# FLYTE-v2_1.net
KiCad netlist of a schematic drawn in EAGLE
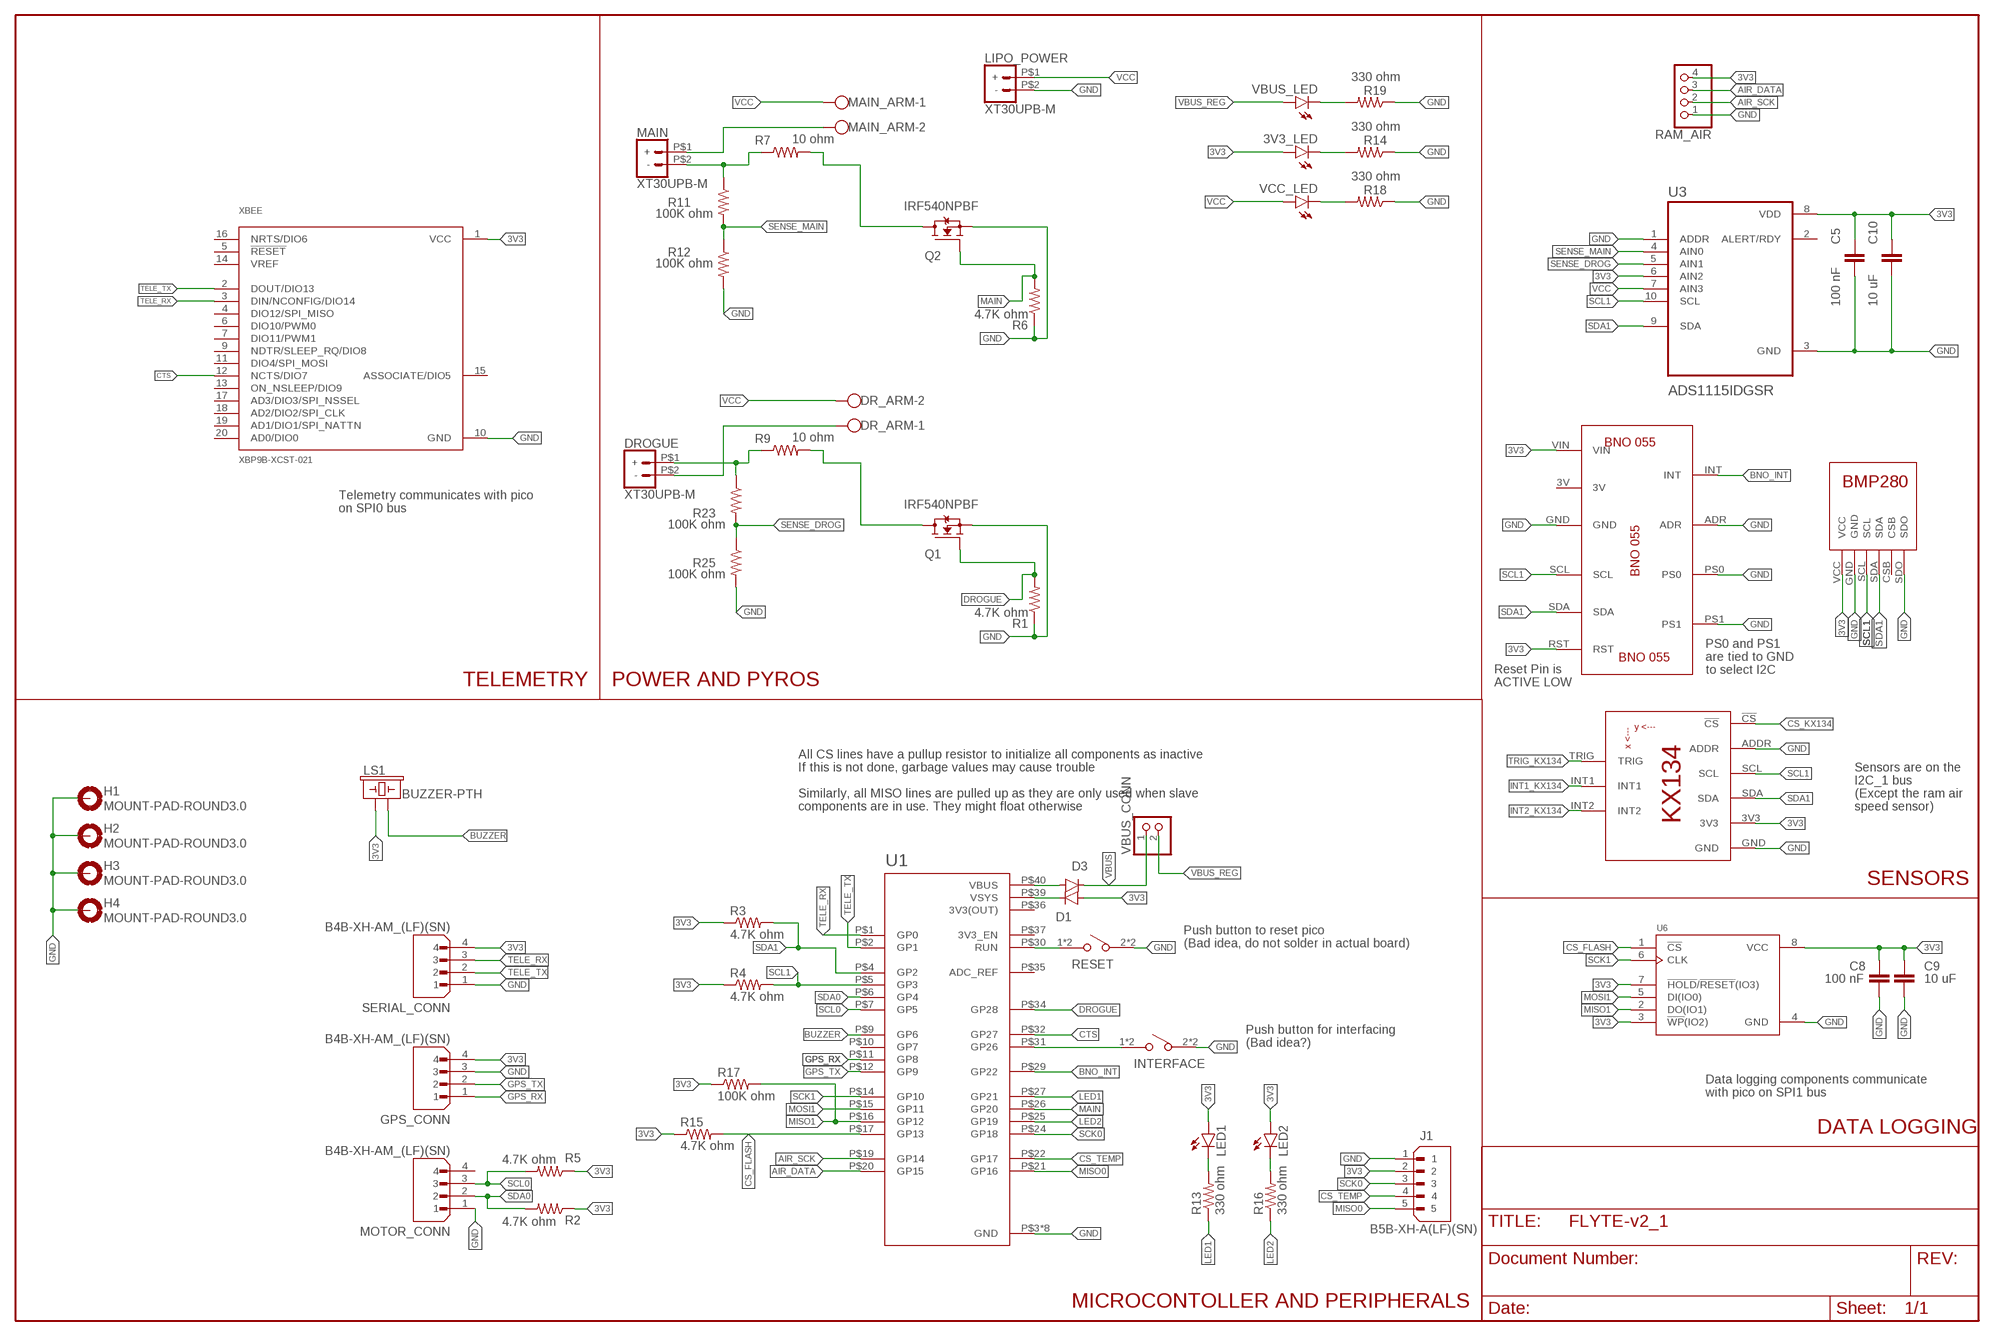
[diagram p0: schematic, sheet 1, part 1 of 2]
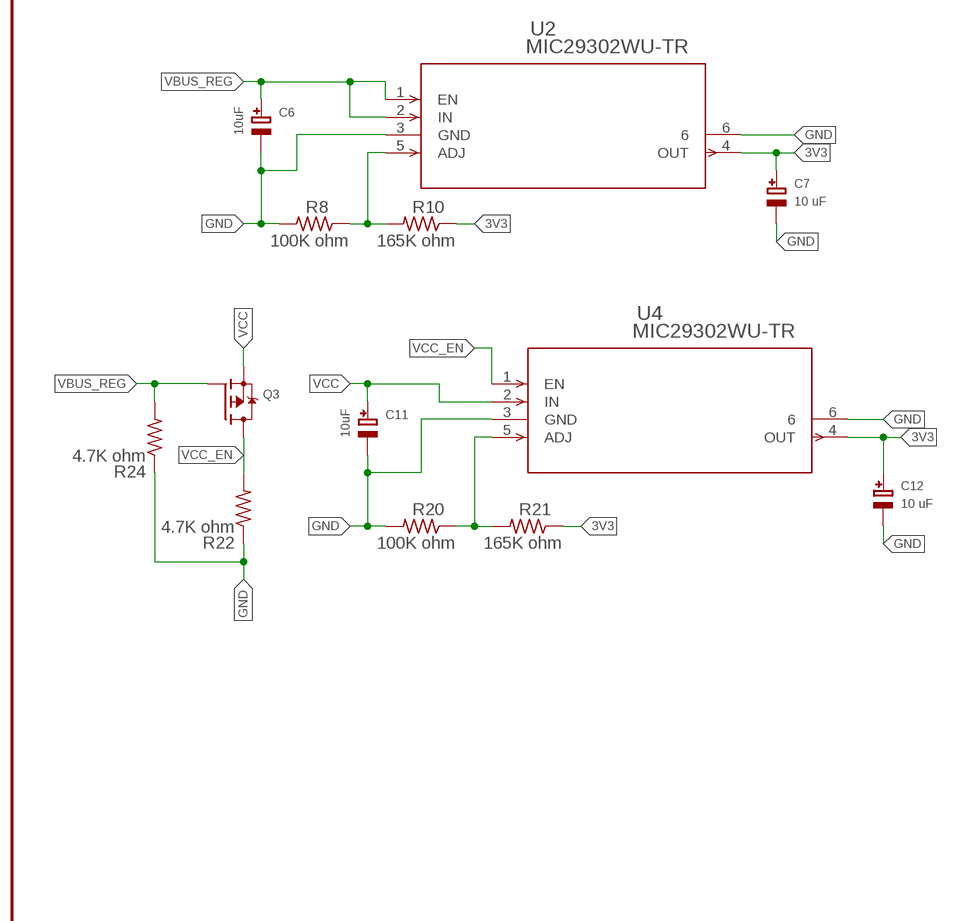
[diagram p1: schematic, sheet 1, part 2 of 2]

(export (version "E")
  (design (tool "Eeschema 10.0.6"))
  (components
    (comp (ref "3V3_LED")
      (value "LEDCHIPLED_1206")
      (footprint "eagle-import:CHIPLED_1206")
      (libsource (lib "eagle-import") (part "LEDCHIPLED_1206"))
    )
    (comp (ref "C5")
      (value "100 nF")
      (footprint "eagle-import:0805")
      (libsource (lib "eagle-import") (part "22UF-0805-6.3V-20%"))
    )
    (comp (ref "C6")
      (value "10uF")
      (footprint "eagle-import:EIA3216-18_A-W")
      (libsource (lib "eagle-import") (part "CAP_TANTALUMA/3216_WAVE"))
    )
    (comp (ref "C7")
      (value "10 uF")
      (footprint "eagle-import:EIA3216-18_A-W")
      (libsource (lib "eagle-import") (part "CAP_TANTALUMA/3216_WAVE"))
    )
    (comp (ref "C8")
      (value "100 nF")
      (footprint "eagle-import:0805")
      (libsource (lib "eagle-import") (part "22UF-0805-6.3V-20%"))
    )
    (comp (ref "C9")
      (value "10 uF")
      (footprint "eagle-import:0805")
      (libsource (lib "eagle-import") (part "22UF-0805-6.3V-20%"))
    )
    (comp (ref "C10")
      (value "10 uF")
      (footprint "eagle-import:0805")
      (libsource (lib "eagle-import") (part "22UF-0805-6.3V-20%"))
    )
    (comp (ref "C11")
      (value "10uF")
      (footprint "eagle-import:EIA3216-18_A-W")
      (libsource (lib "eagle-import") (part "CAP_TANTALUMA/3216_WAVE"))
    )
    (comp (ref "C12")
      (value "10 uF")
      (footprint "eagle-import:EIA3216-18_A-W")
      (libsource (lib "eagle-import") (part "CAP_TANTALUMA/3216_WAVE"))
    )
    (comp (ref "D1")
      (value "1N4004")
      (footprint "eagle-import:DO41-10")
      (libsource (lib "eagle-import") (part "1N4004"))
    )
    (comp (ref "D3")
      (value "1N4004")
      (footprint "eagle-import:DO41-10")
      (libsource (lib "eagle-import") (part "1N4004"))
    )
    (comp (ref "DROGUE")
      (value "XT30UPB-M")
      (footprint "eagle-import:XT30UPB-M")
      (fields (field (name "MF") "amass"))
      (libsource (lib "eagle-import") (part "XT30UPB-M"))
    )
    (comp (ref "DR_ARM")
      (value "W237-102")
      (footprint "eagle-import:W237-102")
      (fields (field (name "MPN") "237-102"))
      (libsource (lib "eagle-import") (part "W237-102"))
    )
    (comp (ref "GPS_CONN")
      (value "B4B-XH-AM_(LF)(SN)")
      (footprint "eagle-import:JST_B4B-XH-AM_(LF)(SN)")
      (fields (field (name "MF") "JST Corporation") (field (name "MP") "B4B-XH-AM (LF)(SN)"))
      (libsource (lib "eagle-import") (part "B4B-XH-AM_(LF)(SN)"))
    )
    (comp (ref "H1")
      (value "MOUNT-PAD-ROUND3.0")
      (footprint "eagle-import:3,0-PAD")
      (libsource (lib "eagle-import") (part "MOUNT-PAD-ROUND3.0"))
    )
    (comp (ref "H2")
      (value "MOUNT-PAD-ROUND3.0")
      (footprint "eagle-import:3,0-PAD")
      (libsource (lib "eagle-import") (part "MOUNT-PAD-ROUND3.0"))
    )
    (comp (ref "H3")
      (value "MOUNT-PAD-ROUND3.0")
      (footprint "eagle-import:3,0-PAD")
      (libsource (lib "eagle-import") (part "MOUNT-PAD-ROUND3.0"))
    )
    (comp (ref "H4")
      (value "MOUNT-PAD-ROUND3.0")
      (footprint "eagle-import:3,0-PAD")
      (libsource (lib "eagle-import") (part "MOUNT-PAD-ROUND3.0"))
    )
    (comp (ref "INTERFACE")
      (value "TS04-66-95-BK-100-SMT")
      (footprint "eagle-import:SW_TS04-66-95-BK-100-SMT")
      (fields (field (name "MF") "CUI Devices"))
      (libsource (lib "eagle-import") (part "TS04-66-95-BK-100-SMT"))
    )
    (comp (ref "J1")
      (value "B5B-XH-A(LF)(SN)")
      (footprint "eagle-import:JST_B5B-XH-A(LF)(SN)")
      (fields (field (name "MF") "JST Sales America Inc."))
      (libsource (lib "eagle-import") (part "B5B-XH-A(LF)(SN)"))
    )
    (comp (ref "LED1")
      (value "LEDCHIPLED_1206")
      (footprint "eagle-import:CHIPLED_1206")
      (libsource (lib "eagle-import") (part "LEDCHIPLED_1206"))
    )
    (comp (ref "LED2")
      (value "LEDCHIPLED_1206")
      (footprint "eagle-import:CHIPLED_1206")
      (libsource (lib "eagle-import") (part "LEDCHIPLED_1206"))
    )
    (comp (ref "LIPO_POWER")
      (value "XT30UPB-M")
      (footprint "eagle-import:XT30UPB-M")
      (fields (field (name "MF") "amass"))
      (libsource (lib "eagle-import") (part "XT30UPB-M"))
    )
    (comp (ref "LS1")
      (value "BUZZER-PTH")
      (footprint "eagle-import:BUZZER-12MM")
      (libsource (lib "eagle-import") (part "BUZZER-PTH"))
    )
    (comp (ref "MAIN")
      (value "XT30UPB-M")
      (footprint "eagle-import:XT30UPB-M")
      (fields (field (name "MF") "amass"))
      (libsource (lib "eagle-import") (part "XT30UPB-M"))
    )
    (comp (ref "MAIN_ARM")
      (value "W237-102")
      (footprint "eagle-import:W237-102")
      (fields (field (name "MPN") "237-102"))
      (libsource (lib "eagle-import") (part "W237-102"))
    )
    (comp (ref "MOTOR_CONN")
      (value "B4B-XH-AM_(LF)(SN)")
      (footprint "eagle-import:JST_B4B-XH-AM_(LF)(SN)")
      (fields (field (name "MF") "JST Corporation") (field (name "MP") "B4B-XH-AM (LF)(SN)"))
      (libsource (lib "eagle-import") (part "B4B-XH-AM_(LF)(SN)"))
    )
    (comp (ref "Q1")
      (value "IRF540NPBF")
      (footprint "eagle-import:TO254P1054X469X1930-3")
      (fields (field (name "MF") "Infineon"))
      (libsource (lib "eagle-import") (part "IRF540NPBF"))
    )
    (comp (ref "Q2")
      (value "IRF540NPBF")
      (footprint "eagle-import:TO254P1054X469X1930-3")
      (fields (field (name "MF") "Infineon"))
      (libsource (lib "eagle-import") (part "IRF540NPBF"))
    )
    (comp (ref "Q3")
      (value "MOSFET-PWIDE")
      (footprint "eagle-import:SOT23-WIDE")
      (libsource (lib "eagle-import") (part "MOSFET-PWIDE"))
    )
    (comp (ref "R1")
      (value "4.7K ohm")
      (footprint "eagle-import:R0805")
      (libsource (lib "eagle-import") (part "R-US_R0805"))
    )
    (comp (ref "R2")
      (value "4.7K ohm")
      (footprint "eagle-import:R0805")
      (libsource (lib "eagle-import") (part "R-US_R0805"))
    )
    (comp (ref "R3")
      (value "4.7K ohm")
      (footprint "eagle-import:R0805")
      (libsource (lib "eagle-import") (part "R-US_R0805"))
    )
    (comp (ref "R4")
      (value "4.7K ohm")
      (footprint "eagle-import:R0805")
      (libsource (lib "eagle-import") (part "R-US_R0805"))
    )
    (comp (ref "R5")
      (value "4.7K ohm")
      (footprint "eagle-import:R0805")
      (libsource (lib "eagle-import") (part "R-US_R0805"))
    )
    (comp (ref "R6")
      (value "4.7K ohm")
      (footprint "eagle-import:R0805")
      (libsource (lib "eagle-import") (part "R-US_R0805"))
    )
    (comp (ref "R7")
      (value "10 ohm")
      (footprint "eagle-import:0207_10")
      (libsource (lib "eagle-import") (part "R-US_0207/10"))
    )
    (comp (ref "R8")
      (value "100K ohm")
      (footprint "eagle-import:R0805")
      (libsource (lib "eagle-import") (part "R-US_R0805"))
    )
    (comp (ref "R9")
      (value "10 ohm")
      (footprint "eagle-import:0207_10")
      (libsource (lib "eagle-import") (part "R-US_0207/10"))
    )
    (comp (ref "R10")
      (value "165K ohm")
      (footprint "eagle-import:R0805")
      (libsource (lib "eagle-import") (part "R-US_R0805"))
    )
    (comp (ref "R11")
      (value "100K ohm")
      (footprint "eagle-import:R0805")
      (libsource (lib "eagle-import") (part "R-US_R0805"))
    )
    (comp (ref "R12")
      (value "100K ohm")
      (footprint "eagle-import:R0805")
      (libsource (lib "eagle-import") (part "R-US_R0805"))
    )
    (comp (ref "R13")
      (value "330 ohm")
      (footprint "eagle-import:R0805")
      (libsource (lib "eagle-import") (part "R-US_R0805"))
    )
    (comp (ref "R14")
      (value "330 ohm")
      (footprint "eagle-import:R0805")
      (libsource (lib "eagle-import") (part "R-US_R0805"))
    )
    (comp (ref "R15")
      (value "4.7K ohm")
      (footprint "eagle-import:R0805")
      (libsource (lib "eagle-import") (part "R-US_R0805"))
    )
    (comp (ref "R16")
      (value "330 ohm")
      (footprint "eagle-import:R0805")
      (libsource (lib "eagle-import") (part "R-US_R0805"))
    )
    (comp (ref "R17")
      (value "100K ohm")
      (footprint "eagle-import:R0805")
      (libsource (lib "eagle-import") (part "R-US_R0805"))
    )
    (comp (ref "R18")
      (value "330 ohm")
      (footprint "eagle-import:R0805")
      (libsource (lib "eagle-import") (part "R-US_R0805"))
    )
    (comp (ref "R19")
      (value "330 ohm")
      (footprint "eagle-import:R0805")
      (libsource (lib "eagle-import") (part "R-US_R0805"))
    )
    (comp (ref "R20")
      (value "100K ohm")
      (footprint "eagle-import:R0805")
      (libsource (lib "eagle-import") (part "R-US_R0805"))
    )
    (comp (ref "R21")
      (value "165K ohm")
      (footprint "eagle-import:R0805")
      (libsource (lib "eagle-import") (part "R-US_R0805"))
    )
    (comp (ref "R22")
      (value "4.7K ohm")
      (footprint "eagle-import:R0805")
      (libsource (lib "eagle-import") (part "R-US_R0805"))
    )
    (comp (ref "R23")
      (value "100K ohm")
      (footprint "eagle-import:R0805")
      (libsource (lib "eagle-import") (part "R-US_R0805"))
    )
    (comp (ref "R24")
      (value "4.7K ohm")
      (footprint "eagle-import:R0805")
      (libsource (lib "eagle-import") (part "R-US_R0805"))
    )
    (comp (ref "R25")
      (value "100K ohm")
      (footprint "eagle-import:R0805")
      (libsource (lib "eagle-import") (part "R-US_R0805"))
    )
    (comp (ref "RAM_AIR")
      (value "PINHD-1X4")
      (footprint "eagle-import:1X04")
      (libsource (lib "eagle-import") (part "PINHD-1X4"))
    )
    (comp (ref "RESET")
      (value "TS04-66-95-BK-100-SMT")
      (footprint "eagle-import:SW_TS04-66-95-BK-100-SMT")
      (fields (field (name "MF") "CUI Devices"))
      (libsource (lib "eagle-import") (part "TS04-66-95-BK-100-SMT"))
    )
    (comp (ref "SERIAL_CONN")
      (value "B4B-XH-AM_(LF)(SN)")
      (footprint "eagle-import:JST_B4B-XH-AM_(LF)(SN)")
      (fields (field (name "MF") "JST Corporation") (field (name "MP") "B4B-XH-AM (LF)(SN)"))
      (libsource (lib "eagle-import") (part "B4B-XH-AM_(LF)(SN)"))
    )
    (comp (ref "U$1")
      (value "BMP280")
      (footprint "eagle-import:BMP280")
      (libsource (lib "eagle-import") (part "BMP280"))
    )
    (comp (ref "U$2")
      (value "KX134-BREAKOUT")
      (footprint "eagle-import:KX134-BREAKOUT")
      (libsource (lib "eagle-import") (part "KX134-BREAKOUT"))
    )
    (comp (ref "U$4")
      (value "BNO055")
      (footprint "eagle-import:BNO055")
      (libsource (lib "eagle-import") (part "BNO055"))
    )
    (comp (ref "U1")
      (value "RASPBERRY_PICO-NO_DEBUG")
      (footprint "eagle-import:PICO-PKG-NO_DEBUG")
      (libsource (lib "eagle-import") (part "RASPBERRY_PICO-NO_DEBUG"))
    )
    (comp (ref "U2")
      (value "MIC29302WU-TR")
      (footprint "eagle-import:TO-263-5_MCH")
      (fields (field (name "COPYRIGHT") "Copyright (C) 2024 Ultra Librarian. All rights reserved."))
      (libsource (lib "eagle-import") (part "MIC29302WU-TR"))
    )
    (comp (ref "U3")
      (value "ADS1115IDGSR")
      (footprint "eagle-import:SOP50P490X110-10N")
      (fields (field (name "MF") "Texas Instruments"))
      (libsource (lib "eagle-import") (part "ADS1115IDGSR"))
    )
    (comp (ref "U4")
      (value "MIC29302WU-TR")
      (footprint "eagle-import:TO-263-5_MCH")
      (fields (field (name "COPYRIGHT") "Copyright (C) 2024 Ultra Librarian. All rights reserved."))
      (libsource (lib "eagle-import") (part "MIC29302WU-TR"))
    )
    (comp (ref "U6")
      (value "W25Q32JVSSIQ")
      (footprint "eagle-import:SOIC127P790X216-8N")
      (fields (field (name "MF") "Winbond"))
      (libsource (lib "eagle-import") (part "W25Q32JVSSIQ"))
    )
    (comp (ref "VBUS_CONN")
      (value "PINHD-1X2")
      (footprint "eagle-import:1X02")
      (libsource (lib "eagle-import") (part "PINHD-1X2"))
    )
    (comp (ref "VBUS_LED")
      (value "LEDCHIPLED_1206")
      (footprint "eagle-import:CHIPLED_1206")
      (libsource (lib "eagle-import") (part "LEDCHIPLED_1206"))
    )
    (comp (ref "VCC_LED")
      (value "LEDCHIPLED_1206")
      (footprint "eagle-import:CHIPLED_1206")
      (libsource (lib "eagle-import") (part "LEDCHIPLED_1206"))
    )
    (comp (ref "XBEE")
      (value "XBP9B-XCST-021")
      (footprint "eagle-import:DIP2200W51P200L3294H279Q20P")
      (fields (field (name "MF") "Digi International"))
      (libsource (lib "eagle-import") (part "XBP9B-XCST-021"))
    )
  )
  (nets
    (net (code "1") (name "/3V3(OUT)") (class "Default")
      (node (ref "U1") (pin "P$36") (pinfunction "3V3(OUT)_P$36") (pintype "power_in"))
    )
    (net (code "2") (name "3V3") (class "Default")
      (node (ref "3V3_LED") (pin "A") (pinfunction "A_A") (pintype "passive"))
      (node (ref "C10") (pin "1") (pinfunction "1_1") (pintype "passive"))
      (node (ref "C12") (pin "+") (pinfunction "+_+") (pintype "passive"))
      (node (ref "C5") (pin "1") (pinfunction "1_1") (pintype "passive"))
      (node (ref "C7") (pin "+") (pinfunction "+_+") (pintype "passive"))
      (node (ref "C8") (pin "2") (pinfunction "2_2") (pintype "passive"))
      (node (ref "C9") (pin "2") (pinfunction "2_2") (pintype "passive"))
      (node (ref "D1") (pin "A") (pinfunction "A_A") (pintype "passive"))
      (node (ref "GPS_CONN") (pin "4") (pinfunction "4_4") (pintype "passive"))
      (node (ref "J1") (pin "2") (pinfunction "2_2") (pintype "passive"))
      (node (ref "LED1") (pin "A") (pinfunction "A_A") (pintype "passive"))
      (node (ref "LED2") (pin "A") (pinfunction "A_A") (pintype "passive"))
      (node (ref "LS1") (pin "+") (pinfunction "1_+") (pintype "passive"))
      (node (ref "R10") (pin "1") (pinfunction "1_1") (pintype "passive"))
      (node (ref "R15") (pin "1") (pinfunction "1_1") (pintype "passive"))
      (node (ref "R17") (pin "1") (pinfunction "1_1") (pintype "passive"))
      (node (ref "R2") (pin "1") (pinfunction "1_1") (pintype "passive"))
      (node (ref "R21") (pin "1") (pinfunction "1_1") (pintype "passive"))
      (node (ref "R3") (pin "1") (pinfunction "1_1") (pintype "passive"))
      (node (ref "R4") (pin "1") (pinfunction "1_1") (pintype "passive"))
      (node (ref "R5") (pin "1") (pinfunction "1_1") (pintype "passive"))
      (node (ref "RAM_AIR") (pin "4") (pinfunction "4_4") (pintype "passive"))
      (node (ref "SERIAL_CONN") (pin "4") (pinfunction "4_4") (pintype "passive"))
      (node (ref "U$1") (pin "VCC") (pinfunction "VCC_VCC") (pintype "bidirectional"))
      (node (ref "U$2") (pin "3V3") (pinfunction "3V3_3V3") (pintype "bidirectional"))
      (node (ref "U$4") (pin "RST") (pinfunction "RST_RST") (pintype "bidirectional"))
      (node (ref "U$4") (pin "VIN") (pinfunction "VIN_VIN") (pintype "bidirectional"))
      (node (ref "U2") (pin "4") (pinfunction "OUT_4") (pintype "output"))
      (node (ref "U3") (pin "6") (pinfunction "AIN2_6") (pintype "input"))
      (node (ref "U3") (pin "8") (pinfunction "VDD_8") (pintype "power_in"))
      (node (ref "U4") (pin "4") (pinfunction "OUT_4") (pintype "output"))
      (node (ref "U6") (pin "3") (pinfunction "~{WP}(IO2)_3") (pintype "bidirectional"))
      (node (ref "U6") (pin "7") (pinfunction "~{HOLD}/~{RESET}(IO3)_7") (pintype "bidirectional"))
      (node (ref "U6") (pin "8") (pinfunction "VCC_8") (pintype "power_in"))
      (node (ref "XBEE") (pin "1") (pinfunction "VCC_1") (pintype "power_in"))
    )
    (net (code "3") (name "AIR_DATA") (class "Default")
      (node (ref "RAM_AIR") (pin "3") (pinfunction "3_3") (pintype "passive"))
      (node (ref "U1") (pin "P$20") (pinfunction "GP15_P$20") (pintype "bidirectional"))
    )
    (net (code "4") (name "AIR_SCK") (class "Default")
      (node (ref "RAM_AIR") (pin "2") (pinfunction "2_2") (pintype "passive"))
      (node (ref "U1") (pin "P$19") (pinfunction "GP14_P$19") (pintype "bidirectional"))
    )
    (net (code "5") (name "BNO_INT") (class "Default")
      (node (ref "U$4") (pin "INT") (pinfunction "INT_INT") (pintype "bidirectional"))
      (node (ref "U1") (pin "P$29") (pinfunction "GP22_P$29") (pintype "bidirectional"))
    )
    (net (code "6") (name "BUZZER") (class "Default")
      (node (ref "LS1") (pin "-") (pinfunction "2_-") (pintype "passive"))
      (node (ref "U1") (pin "P$9") (pinfunction "GP6_P$9") (pintype "bidirectional"))
    )
    (net (code "7") (name "CS_FLASH") (class "Default")
      (node (ref "R15") (pin "2") (pinfunction "2_2") (pintype "passive"))
      (node (ref "U1") (pin "P$17") (pinfunction "GP13_P$17") (pintype "bidirectional"))
      (node (ref "U6") (pin "1") (pinfunction "~{CS}_1") (pintype "input"))
    )
    (net (code "8") (name "CS_KX134") (class "Default")
      (node (ref "U$2") (pin "!CS") (pinfunction "~{CS}_!CS") (pintype "bidirectional"))
    )
    (net (code "9") (name "CS_TEMP") (class "Default")
      (node (ref "J1") (pin "4") (pinfunction "4_4") (pintype "passive"))
      (node (ref "U1") (pin "P$22") (pinfunction "GP17_P$22") (pintype "bidirectional"))
    )
    (net (code "10") (name "CTS") (class "Default")
      (node (ref "U1") (pin "P$32") (pinfunction "GP27_P$32") (pintype "bidirectional"))
      (node (ref "XBEE") (pin "12") (pinfunction "NCTS/DIO7_12") (pintype "bidirectional"))
    )
    (net (code "11") (name "DROGUE") (class "Default")
      (node (ref "Q1") (pin "1") (pinfunction "G_1") (pintype "passive"))
      (node (ref "R1") (pin "2") (pinfunction "2_2") (pintype "passive"))
      (node (ref "U1") (pin "P$34") (pinfunction "GP28_P$34") (pintype "bidirectional"))
    )
    (net (code "12") (name "GND") (class "Default")
      (node (ref "C10") (pin "2") (pinfunction "2_2") (pintype "passive"))
      (node (ref "C11") (pin "-") (pinfunction "-_-") (pintype "passive"))
      (node (ref "C12") (pin "-") (pinfunction "-_-") (pintype "passive"))
      (node (ref "C5") (pin "2") (pinfunction "2_2") (pintype "passive"))
      (node (ref "C6") (pin "-") (pinfunction "-_-") (pintype "passive"))
      (node (ref "C7") (pin "-") (pinfunction "-_-") (pintype "passive"))
      (node (ref "C8") (pin "1") (pinfunction "1_1") (pintype "passive"))
      (node (ref "C9") (pin "1") (pinfunction "1_1") (pintype "passive"))
      (node (ref "GPS_CONN") (pin "3") (pinfunction "3_3") (pintype "passive"))
      (node (ref "H1") (pin "B3,0") (pinfunction "MOUNT_B3,0") (pintype "passive"))
      (node (ref "H2") (pin "B3,0") (pinfunction "MOUNT_B3,0") (pintype "passive"))
      (node (ref "H3") (pin "B3,0") (pinfunction "MOUNT_B3,0") (pintype "passive"))
      (node (ref "H4") (pin "B3,0") (pinfunction "MOUNT_B3,0") (pintype "passive"))
      (node (ref "INTERFACE") (pin "2") (pinfunction "4_2") (pintype "passive"))
      (node (ref "INTERFACE") (pin "4") (pinfunction "4_4") (pintype "passive"))
      (node (ref "J1") (pin "1") (pinfunction "1_1") (pintype "passive"))
      (node (ref "LIPO_POWER") (pin "P$2") (pinfunction "-_P$2") (pintype "passive"))
      (node (ref "MOTOR_CONN") (pin "1") (pinfunction "1_1") (pintype "passive"))
      (node (ref "Q1") (pin "3") (pinfunction "S_3") (pintype "passive"))
      (node (ref "Q2") (pin "3") (pinfunction "S_3") (pintype "passive"))
      (node (ref "R1") (pin "1") (pinfunction "1_1") (pintype "passive"))
      (node (ref "R12") (pin "2") (pinfunction "2_2") (pintype "passive"))
      (node (ref "R14") (pin "1") (pinfunction "1_1") (pintype "passive"))
      (node (ref "R18") (pin "1") (pinfunction "1_1") (pintype "passive"))
      (node (ref "R19") (pin "1") (pinfunction "1_1") (pintype "passive"))
      (node (ref "R20") (pin "2") (pinfunction "2_2") (pintype "passive"))
      (node (ref "R22") (pin "1") (pinfunction "1_1") (pintype "passive"))
      (node (ref "R24") (pin "1") (pinfunction "1_1") (pintype "passive"))
      (node (ref "R25") (pin "2") (pinfunction "2_2") (pintype "passive"))
      (node (ref "R6") (pin "1") (pinfunction "1_1") (pintype "passive"))
      (node (ref "R8") (pin "2") (pinfunction "2_2") (pintype "passive"))
      (node (ref "RAM_AIR") (pin "1") (pinfunction "1_1") (pintype "passive"))
      (node (ref "RESET") (pin "2") (pinfunction "4_2") (pintype "passive"))
      (node (ref "RESET") (pin "4") (pinfunction "4_4") (pintype "passive"))
      (node (ref "SERIAL_CONN") (pin "1") (pinfunction "1_1") (pintype "passive"))
      (node (ref "U$1") (pin "GND") (pinfunction "GND_GND") (pintype "bidirectional"))
      (node (ref "U$1") (pin "SDO") (pinfunction "SDO_SDO") (pintype "bidirectional"))
      (node (ref "U$2") (pin "ADDR") (pinfunction "ADDR_ADDR") (pintype "bidirectional"))
      (node (ref "U$2") (pin "GND") (pinfunction "GND_GND") (pintype "bidirectional"))
      (node (ref "U$4") (pin "ADR") (pinfunction "ADR_ADR") (pintype "bidirectional"))
      (node (ref "U$4") (pin "GND") (pinfunction "GND_GND") (pintype "bidirectional"))
      (node (ref "U$4") (pin "PS0") (pinfunction "PS0_PS0") (pintype "bidirectional"))
      (node (ref "U$4") (pin "PS1") (pinfunction "PS1_PS1") (pintype "bidirectional"))
      (node (ref "U1") (pin "P$13") (pinfunction "GND_P$13") (pintype "power_in"))
      (node (ref "U1") (pin "P$18") (pinfunction "GND_P$18") (pintype "power_in"))
      (node (ref "U1") (pin "P$23") (pinfunction "GND_P$23") (pintype "power_in"))
      (node (ref "U1") (pin "P$28") (pinfunction "GND_P$28") (pintype "power_in"))
      (node (ref "U1") (pin "P$3") (pinfunction "GND_P$3") (pintype "power_in"))
      (node (ref "U1") (pin "P$33") (pinfunction "GND_P$33") (pintype "power_in"))
      (node (ref "U1") (pin "P$38") (pinfunction "GND_P$38") (pintype "power_in"))
      (node (ref "U1") (pin "P$8") (pinfunction "GND_P$8") (pintype "power_in"))
      (node (ref "U2") (pin "3") (pinfunction "GND_3") (pintype "power_in"))
      (node (ref "U2") (pin "6") (pinfunction "6_6") (pintype "passive"))
      (node (ref "U3") (pin "1") (pinfunction "ADDR_1") (pintype "input"))
      (node (ref "U3") (pin "3") (pinfunction "GND_3") (pintype "power_in"))
      (node (ref "U4") (pin "3") (pinfunction "GND_3") (pintype "power_in"))
      (node (ref "U4") (pin "6") (pinfunction "6_6") (pintype "passive"))
      (node (ref "U6") (pin "4") (pinfunction "GND_4") (pintype "power_in"))
      (node (ref "XBEE") (pin "10") (pinfunction "GND_10") (pintype "power_in"))
    )
    (net (code "13") (name "GPS_RX") (class "Default")
      (node (ref "GPS_CONN") (pin "1") (pinfunction "1_1") (pintype "passive"))
      (node (ref "U1") (pin "P$11") (pinfunction "GP8_P$11") (pintype "bidirectional"))
    )
    (net (code "14") (name "GPS_TX") (class "Default")
      (node (ref "GPS_CONN") (pin "2") (pinfunction "2_2") (pintype "passive"))
      (node (ref "U1") (pin "P$12") (pinfunction "GP9_P$12") (pintype "bidirectional"))
    )
    (net (code "15") (name "INT1_KX134") (class "Default")
      (node (ref "U$2") (pin "INT1") (pinfunction "INT1_INT1") (pintype "bidirectional"))
    )
    (net (code "16") (name "INT2_KX134") (class "Default")
      (node (ref "U$2") (pin "INT2") (pinfunction "INT2_INT2") (pintype "bidirectional"))
    )
    (net (code "17") (name "LED1") (class "Default")
      (node (ref "R13") (pin "1") (pinfunction "1_1") (pintype "passive"))
      (node (ref "U1") (pin "P$27") (pinfunction "GP21_P$27") (pintype "bidirectional"))
    )
    (net (code "18") (name "LED2") (class "Default")
      (node (ref "R16") (pin "1") (pinfunction "1_1") (pintype "passive"))
      (node (ref "U1") (pin "P$25") (pinfunction "GP19_P$25") (pintype "bidirectional"))
    )
    (net (code "19") (name "MAIN") (class "Default")
      (node (ref "Q2") (pin "1") (pinfunction "G_1") (pintype "passive"))
      (node (ref "R6") (pin "2") (pinfunction "2_2") (pintype "passive"))
      (node (ref "U1") (pin "P$26") (pinfunction "GP20_P$26") (pintype "bidirectional"))
    )
    (net (code "20") (name "MISO0") (class "Default")
      (node (ref "J1") (pin "5") (pinfunction "5_5") (pintype "passive"))
      (node (ref "U1") (pin "P$21") (pinfunction "GP16_P$21") (pintype "bidirectional"))
    )
    (net (code "21") (name "MISO1") (class "Default")
      (node (ref "R17") (pin "2") (pinfunction "2_2") (pintype "passive"))
      (node (ref "U1") (pin "P$16") (pinfunction "GP12_P$16") (pintype "bidirectional"))
      (node (ref "U6") (pin "2") (pinfunction "DO(IO1)_2") (pintype "bidirectional"))
    )
    (net (code "22") (name "MOSI1") (class "Default")
      (node (ref "U1") (pin "P$15") (pinfunction "GP11_P$15") (pintype "bidirectional"))
      (node (ref "U6") (pin "5") (pinfunction "DI(IO0)_5") (pintype "bidirectional"))
    )
    (net (code "23") (name "Net-(3V3_LED-PadC)") (class "Default")
      (node (ref "3V3_LED") (pin "C") (pinfunction "C_C") (pintype "passive"))
      (node (ref "R14") (pin "2") (pinfunction "2_2") (pintype "passive"))
    )
    (net (code "24") (name "Net-(DROGUE-+)") (class "Default")
      (node (ref "DROGUE") (pin "P$1") (pinfunction "+_P$1") (pintype "passive"))
      (node (ref "R23") (pin "1") (pinfunction "1_1") (pintype "passive"))
      (node (ref "R9") (pin "1") (pinfunction "1_1") (pintype "passive"))
    )
    (net (code "25") (name "Net-(DROGUE--)") (class "Default")
      (node (ref "DROGUE") (pin "P$2") (pinfunction "-_P$2") (pintype "passive"))
      (node (ref "DR_ARM") (pin "1") (pinfunction "KL_1") (pintype "passive"))
    )
    (net (code "26") (name "Net-(LED1-PadC)") (class "Default")
      (node (ref "LED1") (pin "C") (pinfunction "C_C") (pintype "passive"))
      (node (ref "R13") (pin "2") (pinfunction "2_2") (pintype "passive"))
    )
    (net (code "27") (name "Net-(LED2-PadC)") (class "Default")
      (node (ref "LED2") (pin "C") (pinfunction "C_C") (pintype "passive"))
      (node (ref "R16") (pin "2") (pinfunction "2_2") (pintype "passive"))
    )
    (net (code "28") (name "Net-(MAIN-+)") (class "Default")
      (node (ref "MAIN") (pin "P$1") (pinfunction "+_P$1") (pintype "passive"))
      (node (ref "MAIN_ARM") (pin "2") (pinfunction "KL_2") (pintype "passive"))
    )
    (net (code "29") (name "Net-(MAIN--)") (class "Default")
      (node (ref "MAIN") (pin "P$2") (pinfunction "-_P$2") (pintype "passive"))
      (node (ref "R11") (pin "1") (pinfunction "1_1") (pintype "passive"))
      (node (ref "R7") (pin "1") (pinfunction "1_1") (pintype "passive"))
    )
    (net (code "30") (name "Net-(Q1-D)") (class "Default")
      (node (ref "Q1") (pin "2") (pinfunction "D_2") (pintype "passive"))
      (node (ref "R9") (pin "2") (pinfunction "2_2") (pintype "passive"))
    )
    (net (code "31") (name "Net-(Q2-D)") (class "Default")
      (node (ref "Q2") (pin "2") (pinfunction "D_2") (pintype "passive"))
      (node (ref "R7") (pin "2") (pinfunction "2_2") (pintype "passive"))
    )
    (net (code "32") (name "Net-(R18-Pad2)") (class "Default")
      (node (ref "R18") (pin "2") (pinfunction "2_2") (pintype "passive"))
      (node (ref "VCC_LED") (pin "C") (pinfunction "C_C") (pintype "passive"))
    )
    (net (code "33") (name "Net-(R19-Pad2)") (class "Default")
      (node (ref "R19") (pin "2") (pinfunction "2_2") (pintype "passive"))
      (node (ref "VBUS_LED") (pin "C") (pinfunction "C_C") (pintype "passive"))
    )
    (net (code "34") (name "Net-(U1-GP26)") (class "Default")
      (node (ref "INTERFACE") (pin "1") (pinfunction "2_1") (pintype "passive"))
      (node (ref "INTERFACE") (pin "3") (pinfunction "2_3") (pintype "passive"))
      (node (ref "U1") (pin "P$31") (pinfunction "GP26_P$31") (pintype "bidirectional"))
    )
    (net (code "35") (name "Net-(U1-RUN)") (class "Default")
      (node (ref "RESET") (pin "1") (pinfunction "2_1") (pintype "passive"))
      (node (ref "RESET") (pin "3") (pinfunction "2_3") (pintype "passive"))
      (node (ref "U1") (pin "P$30") (pinfunction "RUN_P$30") (pintype "input"))
    )
    (net (code "36") (name "Net-(U1-VBUS)") (class "Default")
      (node (ref "D3") (pin "A") (pinfunction "A_A") (pintype "passive"))
      (node (ref "U1") (pin "P$40") (pinfunction "VBUS_P$40") (pintype "power_in"))
    )
    (net (code "37") (name "Net-(U1-VSYS)") (class "Default")
      (node (ref "D1") (pin "C") (pinfunction "C_C") (pintype "passive"))
      (node (ref "U1") (pin "P$39") (pinfunction "VSYS_P$39") (pintype "power_in"))
    )
    (net (code "38") (name "Net-(U2-ADJ)") (class "Default")
      (node (ref "R10") (pin "2") (pinfunction "2_2") (pintype "passive"))
      (node (ref "R8") (pin "1") (pinfunction "1_1") (pintype "passive"))
      (node (ref "U2") (pin "5") (pinfunction "ADJ_5") (pintype "input"))
    )
    (net (code "39") (name "Net-(U4-ADJ)") (class "Default")
      (node (ref "R20") (pin "1") (pinfunction "1_1") (pintype "passive"))
      (node (ref "R21") (pin "2") (pinfunction "2_2") (pintype "passive"))
      (node (ref "U4") (pin "5") (pinfunction "ADJ_5") (pintype "input"))
    )
    (net (code "40") (name "SCK0") (class "Default")
      (node (ref "J1") (pin "3") (pinfunction "3_3") (pintype "passive"))
      (node (ref "U1") (pin "P$24") (pinfunction "GP18_P$24") (pintype "bidirectional"))
    )
    (net (code "41") (name "SCK1") (class "Default")
      (node (ref "U1") (pin "P$14") (pinfunction "GP10_P$14") (pintype "bidirectional"))
      (node (ref "U6") (pin "6") (pinfunction "CLK_6") (pintype "input"))
    )
    (net (code "42") (name "SCL0") (class "Default")
      (node (ref "MOTOR_CONN") (pin "3") (pinfunction "3_3") (pintype "passive"))
      (node (ref "R5") (pin "2") (pinfunction "2_2") (pintype "passive"))
      (node (ref "U1") (pin "P$7") (pinfunction "GP5_P$7") (pintype "bidirectional"))
    )
    (net (code "43") (name "SCL1") (class "Default")
      (node (ref "R4") (pin "2") (pinfunction "2_2") (pintype "passive"))
      (node (ref "U$1") (pin "SCL") (pinfunction "SCL_SCL") (pintype "bidirectional"))
      (node (ref "U$2") (pin "SCL") (pinfunction "SCL_SCL") (pintype "bidirectional"))
      (node (ref "U$4") (pin "SCL") (pinfunction "SCL_SCL") (pintype "bidirectional"))
      (node (ref "U1") (pin "P$5") (pinfunction "GP3_P$5") (pintype "bidirectional"))
      (node (ref "U3") (pin "10") (pinfunction "SCL_10") (pintype "input"))
    )
    (net (code "44") (name "SDA0") (class "Default")
      (node (ref "MOTOR_CONN") (pin "2") (pinfunction "2_2") (pintype "passive"))
      (node (ref "R2") (pin "2") (pinfunction "2_2") (pintype "passive"))
      (node (ref "U1") (pin "P$6") (pinfunction "GP4_P$6") (pintype "bidirectional"))
    )
    (net (code "45") (name "SDA1") (class "Default")
      (node (ref "R3") (pin "2") (pinfunction "2_2") (pintype "passive"))
      (node (ref "U$1") (pin "SDA") (pinfunction "SDA_SDA") (pintype "bidirectional"))
      (node (ref "U$2") (pin "SDA") (pinfunction "SDA_SDA") (pintype "bidirectional"))
      (node (ref "U$4") (pin "SDA") (pinfunction "SDA_SDA") (pintype "bidirectional"))
      (node (ref "U1") (pin "P$4") (pinfunction "GP2_P$4") (pintype "bidirectional"))
      (node (ref "U3") (pin "9") (pinfunction "SDA_9") (pintype "bidirectional"))
    )
    (net (code "46") (name "SENSE_DROG") (class "Default")
      (node (ref "R23") (pin "2") (pinfunction "2_2") (pintype "passive"))
      (node (ref "R25") (pin "1") (pinfunction "1_1") (pintype "passive"))
      (node (ref "U3") (pin "5") (pinfunction "AIN1_5") (pintype "input"))
    )
    (net (code "47") (name "SENSE_MAIN") (class "Default")
      (node (ref "R11") (pin "2") (pinfunction "2_2") (pintype "passive"))
      (node (ref "R12") (pin "1") (pinfunction "1_1") (pintype "passive"))
      (node (ref "U3") (pin "4") (pinfunction "AIN0_4") (pintype "input"))
    )
    (net (code "48") (name "TELE_RX") (class "Default")
      (node (ref "SERIAL_CONN") (pin "3") (pinfunction "3_3") (pintype "passive"))
      (node (ref "U1") (pin "P$1") (pinfunction "GP0_P$1") (pintype "bidirectional"))
      (node (ref "XBEE") (pin "3") (pinfunction "DIN/NCONFIG/DIO14_3") (pintype "bidirectional"))
    )
    (net (code "49") (name "TELE_TX") (class "Default")
      (node (ref "SERIAL_CONN") (pin "2") (pinfunction "2_2") (pintype "passive"))
      (node (ref "U1") (pin "P$2") (pinfunction "GP1_P$2") (pintype "bidirectional"))
      (node (ref "XBEE") (pin "2") (pinfunction "DOUT/DIO13_2") (pintype "bidirectional"))
    )
    (net (code "50") (name "TRIG_KX134") (class "Default")
      (node (ref "U$2") (pin "TRIG") (pinfunction "TRIG_TRIG") (pintype "bidirectional"))
    )
    (net (code "51") (name "VBUS") (class "Default")
      (node (ref "D3") (pin "C") (pinfunction "C_C") (pintype "passive"))
      (node (ref "VBUS_CONN") (pin "1") (pinfunction "1_1") (pintype "passive"))
    )
    (net (code "52") (name "VBUS_REG") (class "Default")
      (node (ref "C6") (pin "+") (pinfunction "+_+") (pintype "passive"))
      (node (ref "Q3") (pin "1") (pinfunction "G_1") (pintype "passive"))
      (node (ref "R24") (pin "2") (pinfunction "2_2") (pintype "passive"))
      (node (ref "U2") (pin "1") (pinfunction "EN_1") (pintype "input"))
      (node (ref "U2") (pin "2") (pinfunction "IN_2") (pintype "input"))
      (node (ref "VBUS_CONN") (pin "2") (pinfunction "2_2") (pintype "passive"))
      (node (ref "VBUS_LED") (pin "A") (pinfunction "A_A") (pintype "passive"))
    )
    (net (code "53") (name "VCC") (class "Default")
      (node (ref "C11") (pin "+") (pinfunction "+_+") (pintype "passive"))
      (node (ref "DR_ARM") (pin "2") (pinfunction "KL_2") (pintype "passive"))
      (node (ref "LIPO_POWER") (pin "P$1") (pinfunction "+_P$1") (pintype "passive"))
      (node (ref "MAIN_ARM") (pin "1") (pinfunction "KL_1") (pintype "passive"))
      (node (ref "Q3") (pin "2") (pinfunction "S_2") (pintype "passive"))
      (node (ref "U3") (pin "7") (pinfunction "AIN3_7") (pintype "input"))
      (node (ref "U4") (pin "2") (pinfunction "IN_2") (pintype "input"))
      (node (ref "VCC_LED") (pin "A") (pinfunction "A_A") (pintype "passive"))
    )
    (net (code "54") (name "VCC_EN") (class "Default")
      (node (ref "Q3") (pin "3") (pinfunction "D_3") (pintype "passive"))
      (node (ref "R22") (pin "2") (pinfunction "2_2") (pintype "passive"))
      (node (ref "U4") (pin "1") (pinfunction "EN_1") (pintype "input"))
    )
    (net (code "55") (name "unconnected-(MOTOR_CONN-Pad4)") (class "Default")
      (node (ref "MOTOR_CONN") (pin "4") (pinfunction "4_4") (pintype "passive"))
    )
    (net (code "56") (name "unconnected-(U$1-PadCSB)") (class "Default")
      (node (ref "U$1") (pin "CSB") (pinfunction "CSB_CSB") (pintype "bidirectional"))
    )
    (net (code "57") (name "unconnected-(U$4-Pad3V)") (class "Default")
      (node (ref "U$4") (pin "3V") (pinfunction "3V_3V") (pintype "bidirectional"))
    )
    (net (code "58") (name "unconnected-(U1-3V3_EN-PadP$37)") (class "Default")
      (node (ref "U1") (pin "P$37") (pinfunction "3V3_EN_P$37") (pintype "input"))
    )
    (net (code "59") (name "unconnected-(U1-ADC_REF-PadP$35)") (class "Default")
      (node (ref "U1") (pin "P$35") (pinfunction "ADC_REF_P$35") (pintype "input"))
    )
    (net (code "60") (name "unconnected-(U1-GP7-PadP$10)") (class "Default")
      (node (ref "U1") (pin "P$10") (pinfunction "GP7_P$10") (pintype "bidirectional"))
    )
    (net (code "61") (name "unconnected-(U3-ALERT{slash}RDY-Pad2)") (class "Default")
      (node (ref "U3") (pin "2") (pinfunction "ALERT/RDY_2") (pintype "output"))
    )
    (net (code "62") (name "unconnected-(XBEE-AD0{slash}DIO0-Pad20)") (class "Default")
      (node (ref "XBEE") (pin "20") (pinfunction "AD0/DIO0_20") (pintype "bidirectional"))
    )
    (net (code "63") (name "unconnected-(XBEE-AD1{slash}DIO1{slash}SPI_NATTN-Pad19)") (class "Default")
      (node (ref "XBEE") (pin "19") (pinfunction "AD1/DIO1/SPI_NATTN_19") (pintype "bidirectional"))
    )
    (net (code "64") (name "unconnected-(XBEE-AD2{slash}DIO2{slash}SPI_CLK-Pad18)") (class "Default")
      (node (ref "XBEE") (pin "18") (pinfunction "AD2/DIO2/SPI_CLK_18") (pintype "bidirectional"))
    )
    (net (code "65") (name "unconnected-(XBEE-AD3{slash}DIO3{slash}SPI_NSSEL-Pad17)") (class "Default")
      (node (ref "XBEE") (pin "17") (pinfunction "AD3/DIO3/SPI_NSSEL_17") (pintype "bidirectional"))
    )
    (net (code "66") (name "unconnected-(XBEE-ASSOCIATE{slash}DIO5-Pad15)") (class "Default")
      (node (ref "XBEE") (pin "15") (pinfunction "ASSOCIATE/DIO5_15") (pintype "output"))
    )
    (net (code "67") (name "unconnected-(XBEE-DIO4{slash}SPI_MOSI-Pad11)") (class "Default")
      (node (ref "XBEE") (pin "11") (pinfunction "DIO4/SPI_MOSI_11") (pintype "bidirectional"))
    )
    (net (code "68") (name "unconnected-(XBEE-DIO10{slash}PWM0-Pad6)") (class "Default")
      (node (ref "XBEE") (pin "6") (pinfunction "DIO10/PWM0_6") (pintype "bidirectional"))
    )
    (net (code "69") (name "unconnected-(XBEE-DIO11{slash}PWM1-Pad7)") (class "Default")
      (node (ref "XBEE") (pin "7") (pinfunction "DIO11/PWM1_7") (pintype "bidirectional"))
    )
    (net (code "70") (name "unconnected-(XBEE-DIO12{slash}SPI_MISO-Pad4)") (class "Default")
      (node (ref "XBEE") (pin "4") (pinfunction "DIO12/SPI_MISO_4") (pintype "bidirectional"))
    )
    (net (code "71") (name "unconnected-(XBEE-NDTR{slash}SLEEP_RQ{slash}DIO8-Pad9)") (class "Default")
      (node (ref "XBEE") (pin "9") (pinfunction "NDTR/SLEEP_RQ/DIO8_9") (pintype "bidirectional"))
    )
    (net (code "72") (name "unconnected-(XBEE-NRTS{slash}DIO6-Pad16)") (class "Default")
      (node (ref "XBEE") (pin "16") (pinfunction "NRTS/DIO6_16") (pintype "input"))
    )
    (net (code "73") (name "unconnected-(XBEE-ON_NSLEEP{slash}DIO9-Pad13)") (class "Default")
      (node (ref "XBEE") (pin "13") (pinfunction "ON_NSLEEP/DIO9_13") (pintype "bidirectional"))
    )
    (net (code "74") (name "unconnected-(XBEE-VREF-Pad14)") (class "Default")
      (node (ref "XBEE") (pin "14") (pinfunction "VREF_14") (pintype "input"))
    )
    (net (code "75") (name "unconnected-(XBEE-~{RESET}-Pad5)") (class "Default")
      (node (ref "XBEE") (pin "5") (pinfunction "~{RESET}_5") (pintype "input"))
    )
  )
)
